# mini_keyboard_switchs.net
KiCad netlist of a schematic drawn in EAGLE
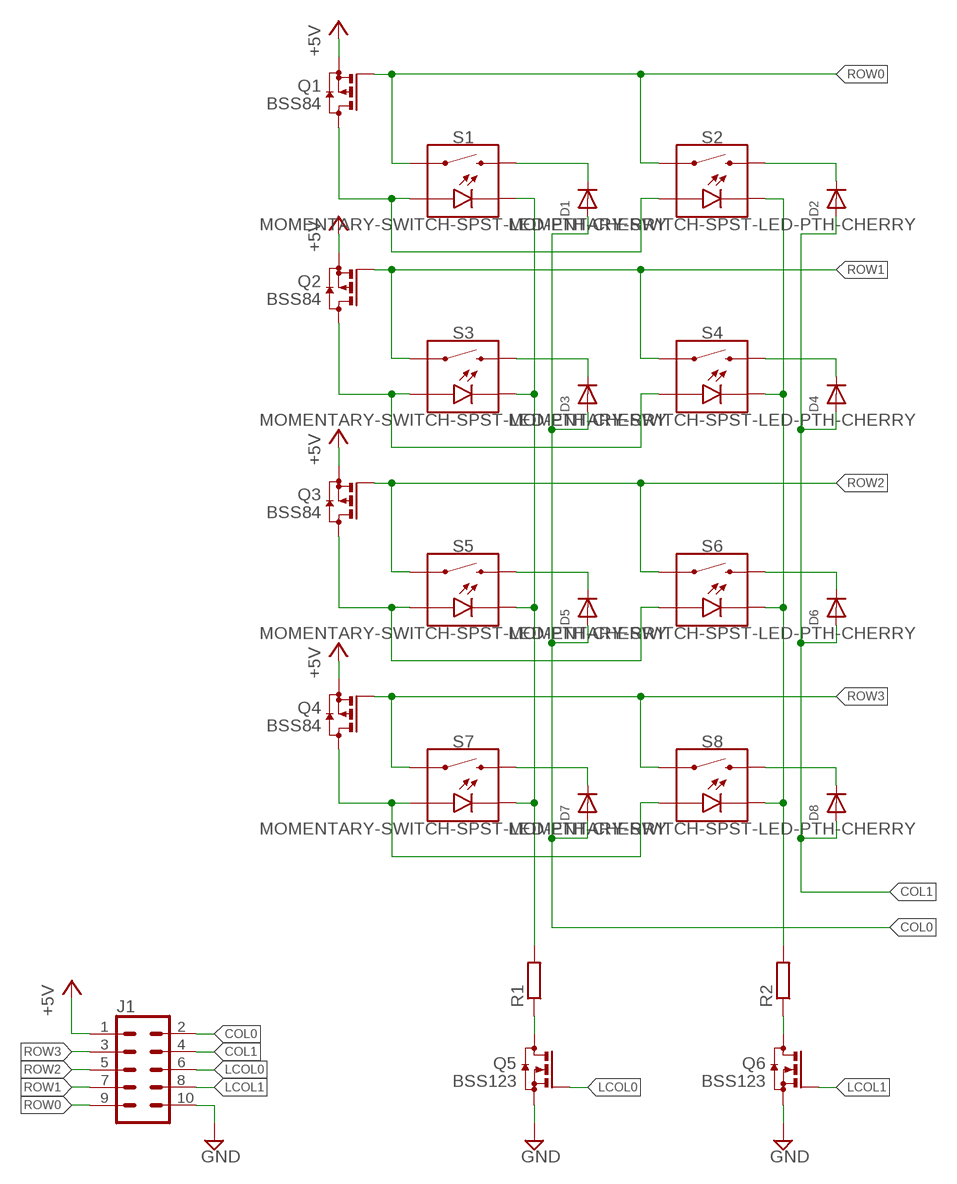
[diagram p0: schematic, sheet 1]

(export (version "E")
  (design (tool "Eeschema 10.0.6"))
  (components
    (comp (ref "D1")
      (value "DIODESOD-323F")
      (footprint "eagle-import:SOD-323F")
      (libsource (lib "eagle-import") (part "DIODESOD-323F"))
    )
    (comp (ref "D2")
      (value "DIODESOD-323F")
      (footprint "eagle-import:SOD-323F")
      (libsource (lib "eagle-import") (part "DIODESOD-323F"))
    )
    (comp (ref "D3")
      (value "DIODESOD-323F")
      (footprint "eagle-import:SOD-323F")
      (libsource (lib "eagle-import") (part "DIODESOD-323F"))
    )
    (comp (ref "D4")
      (value "DIODESOD-323F")
      (footprint "eagle-import:SOD-323F")
      (libsource (lib "eagle-import") (part "DIODESOD-323F"))
    )
    (comp (ref "D5")
      (value "DIODESOD-323F")
      (footprint "eagle-import:SOD-323F")
      (libsource (lib "eagle-import") (part "DIODESOD-323F"))
    )
    (comp (ref "D6")
      (value "DIODESOD-323F")
      (footprint "eagle-import:SOD-323F")
      (libsource (lib "eagle-import") (part "DIODESOD-323F"))
    )
    (comp (ref "D7")
      (value "DIODESOD-323F")
      (footprint "eagle-import:SOD-323F")
      (libsource (lib "eagle-import") (part "DIODESOD-323F"))
    )
    (comp (ref "D8")
      (value "DIODESOD-323F")
      (footprint "eagle-import:SOD-323F")
      (libsource (lib "eagle-import") (part "DIODESOD-323F"))
    )
    (comp (ref "J1")
      (value "CONN_05X2PTH")
      (footprint "eagle-import:2X5")
      (libsource (lib "eagle-import") (part "CONN_05X2PTH"))
    )
    (comp (ref "Q1")
      (value "BSS84")
      (footprint "eagle-import:SOT23")
      (libsource (lib "eagle-import") (part "BSS84"))
    )
    (comp (ref "Q2")
      (value "BSS84")
      (footprint "eagle-import:SOT23")
      (libsource (lib "eagle-import") (part "BSS84"))
    )
    (comp (ref "Q3")
      (value "BSS84")
      (footprint "eagle-import:SOT23")
      (libsource (lib "eagle-import") (part "BSS84"))
    )
    (comp (ref "Q4")
      (value "BSS84")
      (footprint "eagle-import:SOT23")
      (libsource (lib "eagle-import") (part "BSS84"))
    )
    (comp (ref "Q5")
      (value "BSS123")
      (footprint "eagle-import:SOT23")
      (libsource (lib "eagle-import") (part "BSS123"))
    )
    (comp (ref "Q6")
      (value "BSS123")
      (footprint "eagle-import:SOT23")
      (libsource (lib "eagle-import") (part "BSS123"))
    )
    (comp (ref "R1")
      (value "R-EU_R0603")
      (footprint "eagle-import:R0603")
      (libsource (lib "eagle-import") (part "R-EU_R0603"))
    )
    (comp (ref "R2")
      (value "R-EU_R0603")
      (footprint "eagle-import:R0603")
      (libsource (lib "eagle-import") (part "R-EU_R0603"))
    )
    (comp (ref "S1")
      (value "MOMENTARY-SWITCH-SPST-LED-PTH-CHERRY")
      (footprint "eagle-import:CHERRY-MX-LED")
      (libsource (lib "eagle-import") (part "MOMENTARY-SWITCH-SPST-LED-PTH-CHERRY"))
    )
    (comp (ref "S2")
      (value "MOMENTARY-SWITCH-SPST-LED-PTH-CHERRY")
      (footprint "eagle-import:CHERRY-MX-LED")
      (libsource (lib "eagle-import") (part "MOMENTARY-SWITCH-SPST-LED-PTH-CHERRY"))
    )
    (comp (ref "S3")
      (value "MOMENTARY-SWITCH-SPST-LED-PTH-CHERRY")
      (footprint "eagle-import:CHERRY-MX-LED")
      (libsource (lib "eagle-import") (part "MOMENTARY-SWITCH-SPST-LED-PTH-CHERRY"))
    )
    (comp (ref "S4")
      (value "MOMENTARY-SWITCH-SPST-LED-PTH-CHERRY")
      (footprint "eagle-import:CHERRY-MX-LED")
      (libsource (lib "eagle-import") (part "MOMENTARY-SWITCH-SPST-LED-PTH-CHERRY"))
    )
    (comp (ref "S5")
      (value "MOMENTARY-SWITCH-SPST-LED-PTH-CHERRY")
      (footprint "eagle-import:CHERRY-MX-LED")
      (libsource (lib "eagle-import") (part "MOMENTARY-SWITCH-SPST-LED-PTH-CHERRY"))
    )
    (comp (ref "S6")
      (value "MOMENTARY-SWITCH-SPST-LED-PTH-CHERRY")
      (footprint "eagle-import:CHERRY-MX-LED")
      (libsource (lib "eagle-import") (part "MOMENTARY-SWITCH-SPST-LED-PTH-CHERRY"))
    )
    (comp (ref "S7")
      (value "MOMENTARY-SWITCH-SPST-LED-PTH-CHERRY")
      (footprint "eagle-import:CHERRY-MX-LED")
      (libsource (lib "eagle-import") (part "MOMENTARY-SWITCH-SPST-LED-PTH-CHERRY"))
    )
    (comp (ref "S8")
      (value "MOMENTARY-SWITCH-SPST-LED-PTH-CHERRY")
      (footprint "eagle-import:CHERRY-MX-LED")
      (libsource (lib "eagle-import") (part "MOMENTARY-SWITCH-SPST-LED-PTH-CHERRY"))
    )
  )
  (nets
    (net (code "1") (name "+5V") (class "Default")
      (node (ref "J1") (pin "1") (pinfunction "1_1") (pintype "passive"))
      (node (ref "Q1") (pin "2") (pinfunction "S_2") (pintype "passive"))
      (node (ref "Q2") (pin "2") (pinfunction "S_2") (pintype "passive"))
      (node (ref "Q3") (pin "2") (pinfunction "S_2") (pintype "passive"))
      (node (ref "Q4") (pin "2") (pinfunction "S_2") (pintype "passive"))
    )
    (net (code "2") (name "COL0") (class "Default")
      (node (ref "D1") (pin "A") (pinfunction "A_A") (pintype "passive"))
      (node (ref "D3") (pin "A") (pinfunction "A_A") (pintype "passive"))
      (node (ref "D5") (pin "A") (pinfunction "A_A") (pintype "passive"))
      (node (ref "D7") (pin "A") (pinfunction "A_A") (pintype "passive"))
      (node (ref "J1") (pin "2") (pinfunction "2_2") (pintype "passive"))
    )
    (net (code "3") (name "COL1") (class "Default")
      (node (ref "D2") (pin "A") (pinfunction "A_A") (pintype "passive"))
      (node (ref "D4") (pin "A") (pinfunction "A_A") (pintype "passive"))
      (node (ref "D6") (pin "A") (pinfunction "A_A") (pintype "passive"))
      (node (ref "D8") (pin "A") (pinfunction "A_A") (pintype "passive"))
      (node (ref "J1") (pin "4") (pinfunction "4_4") (pintype "passive"))
    )
    (net (code "4") (name "GND") (class "Default")
      (node (ref "J1") (pin "10") (pinfunction "10_10") (pintype "passive"))
      (node (ref "Q5") (pin "2") (pinfunction "S_2") (pintype "passive"))
      (node (ref "Q6") (pin "2") (pinfunction "S_2") (pintype "passive"))
    )
    (net (code "5") (name "LCOL0") (class "Default")
      (node (ref "J1") (pin "6") (pinfunction "6_6") (pintype "passive"))
      (node (ref "Q5") (pin "1") (pinfunction "G_1") (pintype "passive"))
    )
    (net (code "6") (name "LCOL1") (class "Default")
      (node (ref "J1") (pin "8") (pinfunction "8_8") (pintype "passive"))
      (node (ref "Q6") (pin "1") (pinfunction "G_1") (pintype "passive"))
    )
    (net (code "7") (name "Net-(Q1-D)") (class "Default")
      (node (ref "Q1") (pin "3") (pinfunction "D_3") (pintype "passive"))
      (node (ref "S1") (pin "A") (pinfunction "A_A") (pintype "passive"))
      (node (ref "S2") (pin "A") (pinfunction "A_A") (pintype "passive"))
    )
    (net (code "8") (name "Net-(Q2-D)") (class "Default")
      (node (ref "Q2") (pin "3") (pinfunction "D_3") (pintype "passive"))
      (node (ref "S3") (pin "A") (pinfunction "A_A") (pintype "passive"))
      (node (ref "S4") (pin "A") (pinfunction "A_A") (pintype "passive"))
    )
    (net (code "9") (name "Net-(Q3-D)") (class "Default")
      (node (ref "Q3") (pin "3") (pinfunction "D_3") (pintype "passive"))
      (node (ref "S5") (pin "A") (pinfunction "A_A") (pintype "passive"))
      (node (ref "S6") (pin "A") (pinfunction "A_A") (pintype "passive"))
    )
    (net (code "10") (name "Net-(Q4-D)") (class "Default")
      (node (ref "Q4") (pin "3") (pinfunction "D_3") (pintype "passive"))
      (node (ref "S7") (pin "A") (pinfunction "A_A") (pintype "passive"))
      (node (ref "S8") (pin "A") (pinfunction "A_A") (pintype "passive"))
    )
    (net (code "11") (name "Net-(Q5-D)") (class "Default")
      (node (ref "Q5") (pin "3") (pinfunction "D_3") (pintype "passive"))
      (node (ref "R1") (pin "1") (pinfunction "1_1") (pintype "passive"))
    )
    (net (code "12") (name "Net-(Q6-D)") (class "Default")
      (node (ref "Q6") (pin "3") (pinfunction "D_3") (pintype "passive"))
      (node (ref "R2") (pin "1") (pinfunction "1_1") (pintype "passive"))
    )
    (net (code "13") (name "Net-(S1-2)") (class "Default")
      (node (ref "D1") (pin "C") (pinfunction "C_C") (pintype "passive"))
      (node (ref "S1") (pin "S2") (pinfunction "2_S2") (pintype "passive"))
    )
    (net (code "14") (name "Net-(S1-C)") (class "Default")
      (node (ref "R1") (pin "2") (pinfunction "2_2") (pintype "passive"))
      (node (ref "S1") (pin "K") (pinfunction "C_K") (pintype "passive"))
      (node (ref "S3") (pin "K") (pinfunction "C_K") (pintype "passive"))
      (node (ref "S5") (pin "K") (pinfunction "C_K") (pintype "passive"))
      (node (ref "S7") (pin "K") (pinfunction "C_K") (pintype "passive"))
    )
    (net (code "15") (name "Net-(S2-2)") (class "Default")
      (node (ref "D2") (pin "C") (pinfunction "C_C") (pintype "passive"))
      (node (ref "S2") (pin "S2") (pinfunction "2_S2") (pintype "passive"))
    )
    (net (code "16") (name "Net-(S2-C)") (class "Default")
      (node (ref "R2") (pin "2") (pinfunction "2_2") (pintype "passive"))
      (node (ref "S2") (pin "K") (pinfunction "C_K") (pintype "passive"))
      (node (ref "S4") (pin "K") (pinfunction "C_K") (pintype "passive"))
      (node (ref "S6") (pin "K") (pinfunction "C_K") (pintype "passive"))
      (node (ref "S8") (pin "K") (pinfunction "C_K") (pintype "passive"))
    )
    (net (code "17") (name "Net-(S3-2)") (class "Default")
      (node (ref "D3") (pin "C") (pinfunction "C_C") (pintype "passive"))
      (node (ref "S3") (pin "S2") (pinfunction "2_S2") (pintype "passive"))
    )
    (net (code "18") (name "Net-(S4-2)") (class "Default")
      (node (ref "D4") (pin "C") (pinfunction "C_C") (pintype "passive"))
      (node (ref "S4") (pin "S2") (pinfunction "2_S2") (pintype "passive"))
    )
    (net (code "19") (name "Net-(S5-2)") (class "Default")
      (node (ref "D5") (pin "C") (pinfunction "C_C") (pintype "passive"))
      (node (ref "S5") (pin "S2") (pinfunction "2_S2") (pintype "passive"))
    )
    (net (code "20") (name "Net-(S6-2)") (class "Default")
      (node (ref "D6") (pin "C") (pinfunction "C_C") (pintype "passive"))
      (node (ref "S6") (pin "S2") (pinfunction "2_S2") (pintype "passive"))
    )
    (net (code "21") (name "Net-(S7-2)") (class "Default")
      (node (ref "D7") (pin "C") (pinfunction "C_C") (pintype "passive"))
      (node (ref "S7") (pin "S2") (pinfunction "2_S2") (pintype "passive"))
    )
    (net (code "22") (name "Net-(S8-2)") (class "Default")
      (node (ref "D8") (pin "C") (pinfunction "C_C") (pintype "passive"))
      (node (ref "S8") (pin "S2") (pinfunction "2_S2") (pintype "passive"))
    )
    (net (code "23") (name "ROW0") (class "Default")
      (node (ref "J1") (pin "9") (pinfunction "9_9") (pintype "passive"))
      (node (ref "Q1") (pin "1") (pinfunction "G_1") (pintype "passive"))
      (node (ref "S1") (pin "S1") (pinfunction "1_S1") (pintype "passive"))
      (node (ref "S2") (pin "S1") (pinfunction "1_S1") (pintype "passive"))
    )
    (net (code "24") (name "ROW1") (class "Default")
      (node (ref "J1") (pin "7") (pinfunction "7_7") (pintype "passive"))
      (node (ref "Q2") (pin "1") (pinfunction "G_1") (pintype "passive"))
      (node (ref "S3") (pin "S1") (pinfunction "1_S1") (pintype "passive"))
      (node (ref "S4") (pin "S1") (pinfunction "1_S1") (pintype "passive"))
    )
    (net (code "25") (name "ROW2") (class "Default")
      (node (ref "J1") (pin "5") (pinfunction "5_5") (pintype "passive"))
      (node (ref "Q3") (pin "1") (pinfunction "G_1") (pintype "passive"))
      (node (ref "S5") (pin "S1") (pinfunction "1_S1") (pintype "passive"))
      (node (ref "S6") (pin "S1") (pinfunction "1_S1") (pintype "passive"))
    )
    (net (code "26") (name "ROW3") (class "Default")
      (node (ref "J1") (pin "3") (pinfunction "3_3") (pintype "passive"))
      (node (ref "Q4") (pin "1") (pinfunction "G_1") (pintype "passive"))
      (node (ref "S7") (pin "S1") (pinfunction "1_S1") (pintype "passive"))
      (node (ref "S8") (pin "S1") (pinfunction "1_S1") (pintype "passive"))
    )
  )
)
